# nixie_ctrl_board.net
KiCad netlist of a schematic drawn in EAGLE
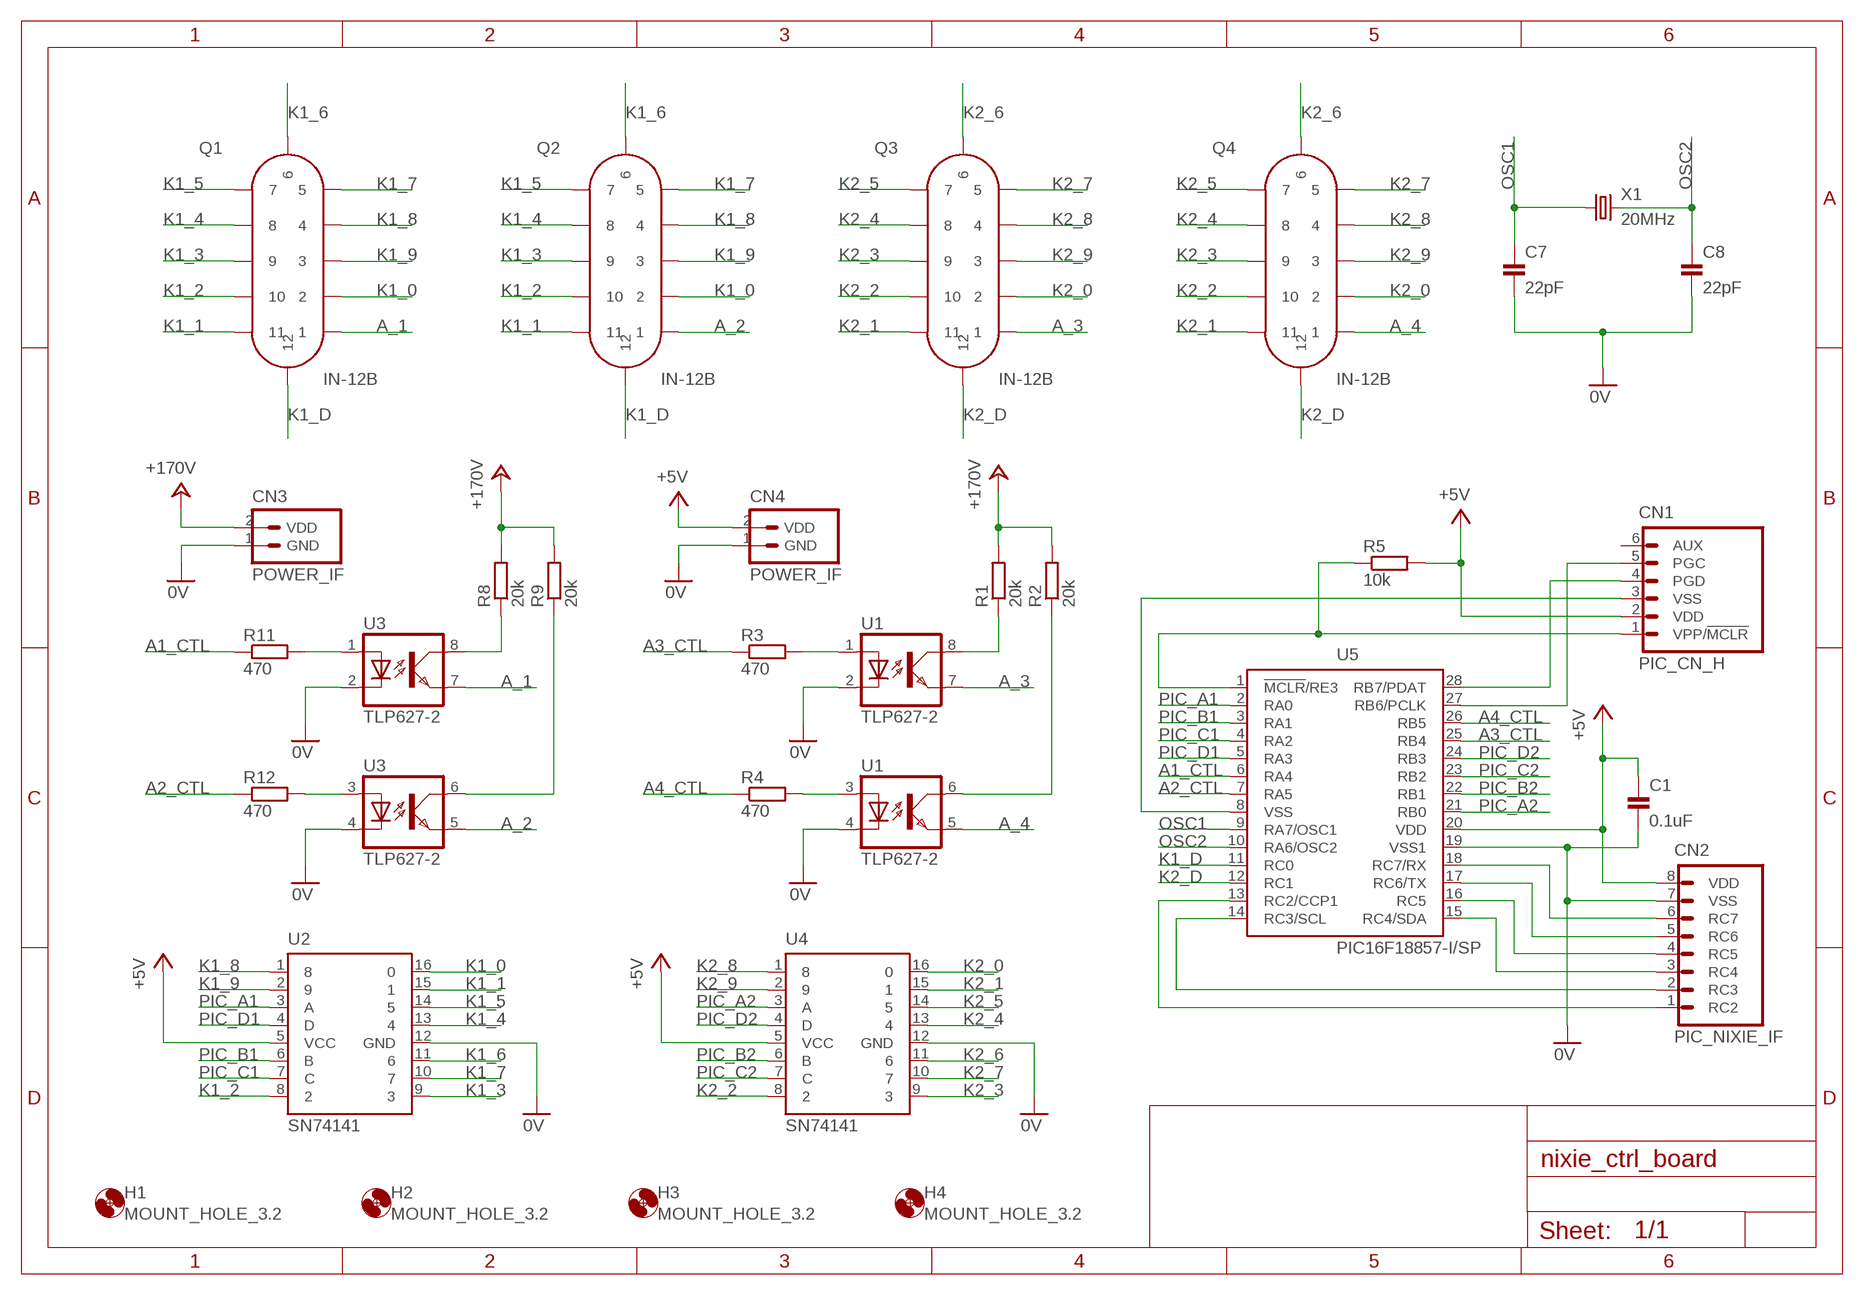
[diagram p0: schematic, sheet 1]

(export (version "E")
  (design (tool "Eeschema 10.0.6"))
  (components
    (comp (ref "C1")
      (value "0.1uF")
      (footprint "eagle-import:CAP_100MIL")
      (libsource (lib "eagle-import") (part "CAP_100MIL"))
    )
    (comp (ref "C7")
      (value "22pF")
      (footprint "eagle-import:CAP_100MIL")
      (libsource (lib "eagle-import") (part "CAP_100MIL"))
    )
    (comp (ref "C8")
      (value "22pF")
      (footprint "eagle-import:CAP_100MIL")
      (libsource (lib "eagle-import") (part "CAP_100MIL"))
    )
    (comp (ref "CN1")
      (value "PIC_CN_H")
      (footprint "eagle-import:HEADER_6PIN")
      (libsource (lib "eagle-import") (part "PIC_CN_H"))
    )
    (comp (ref "CN2")
      (value "PIC_NIXIE_IF")
      (footprint "eagle-import:PIC_IF_NIXIE_8PIN")
      (libsource (lib "eagle-import") (part "PIC_NIXIE_IF"))
    )
    (comp (ref "CN3")
      (value "POWER_IF")
      (footprint "eagle-import:HEADER_2PIN_POWER_IF")
      (libsource (lib "eagle-import") (part "POWER_IF"))
    )
    (comp (ref "CN4")
      (value "POWER_IF")
      (footprint "eagle-import:HEADER_2PIN_POWER_IF")
      (libsource (lib "eagle-import") (part "POWER_IF"))
    )
    (comp (ref "H1")
      (value "MOUNT_HOLE_3.2")
      (footprint "eagle-import:3,2")
      (libsource (lib "eagle-import") (part "MOUNT_HOLE_3.2"))
    )
    (comp (ref "H2")
      (value "MOUNT_HOLE_3.2")
      (footprint "eagle-import:3,2")
      (libsource (lib "eagle-import") (part "MOUNT_HOLE_3.2"))
    )
    (comp (ref "H3")
      (value "MOUNT_HOLE_3.2")
      (footprint "eagle-import:3,2")
      (libsource (lib "eagle-import") (part "MOUNT_HOLE_3.2"))
    )
    (comp (ref "H4")
      (value "MOUNT_HOLE_3.2")
      (footprint "eagle-import:3,2")
      (libsource (lib "eagle-import") (part "MOUNT_HOLE_3.2"))
    )
    (comp (ref "Q1")
      (value "IN-12B")
      (footprint "eagle-import:IN-12")
      (libsource (lib "eagle-import") (part "IN-12B"))
    )
    (comp (ref "Q2")
      (value "IN-12B")
      (footprint "eagle-import:IN-12")
      (libsource (lib "eagle-import") (part "IN-12B"))
    )
    (comp (ref "Q3")
      (value "IN-12B")
      (footprint "eagle-import:IN-12")
      (libsource (lib "eagle-import") (part "IN-12B"))
    )
    (comp (ref "Q4")
      (value "IN-12B")
      (footprint "eagle-import:IN-12")
      (libsource (lib "eagle-import") (part "IN-12B"))
    )
    (comp (ref "R1")
      (value "20k")
      (footprint "eagle-import:RESISTOR_0207_300MIL")
      (libsource (lib "eagle-import") (part "RESISTOR_300MIL"))
    )
    (comp (ref "R2")
      (value "20k")
      (footprint "eagle-import:RESISTOR_0207_300MIL")
      (libsource (lib "eagle-import") (part "RESISTOR_300MIL"))
    )
    (comp (ref "R3")
      (value "470")
      (footprint "eagle-import:RESISTOR_0204_200MIL")
      (libsource (lib "eagle-import") (part "RESISTOR_200MIL"))
    )
    (comp (ref "R4")
      (value "470")
      (footprint "eagle-import:RESISTOR_0204_200MIL")
      (libsource (lib "eagle-import") (part "RESISTOR_200MIL"))
    )
    (comp (ref "R5")
      (value "10k")
      (footprint "eagle-import:RESISTOR_0204_200MIL")
      (libsource (lib "eagle-import") (part "RESISTOR_200MIL"))
    )
    (comp (ref "R8")
      (value "20k")
      (footprint "eagle-import:RESISTOR_0207_300MIL")
      (libsource (lib "eagle-import") (part "RESISTOR_300MIL"))
    )
    (comp (ref "R9")
      (value "20k")
      (footprint "eagle-import:RESISTOR_0207_300MIL")
      (libsource (lib "eagle-import") (part "RESISTOR_300MIL"))
    )
    (comp (ref "R11")
      (value "470")
      (footprint "eagle-import:RESISTOR_0204_200MIL")
      (libsource (lib "eagle-import") (part "RESISTOR_200MIL"))
    )
    (comp (ref "R12")
      (value "470")
      (footprint "eagle-import:RESISTOR_0204_200MIL")
      (libsource (lib "eagle-import") (part "RESISTOR_200MIL"))
    )
    (comp (ref "U1")
      (value "TLP627-2")
      (footprint "eagle-import:DIL08")
      (libsource (lib "eagle-import") (part "TLP627-2"))
    )
    (comp (ref "U2")
      (value "SN74141")
      (footprint "eagle-import:DIL16")
      (libsource (lib "eagle-import") (part "SN74141"))
    )
    (comp (ref "U3")
      (value "TLP627-2")
      (footprint "eagle-import:DIL08")
      (libsource (lib "eagle-import") (part "TLP627-2"))
    )
    (comp (ref "U4")
      (value "SN74141")
      (footprint "eagle-import:DIL16")
      (libsource (lib "eagle-import") (part "SN74141"))
    )
    (comp (ref "U5")
      (value "PIC16F18857-I/SP")
      (footprint "eagle-import:DIL28-3")
      (libsource (lib "eagle-import") (part "PIC16F18857-I/SP"))
    )
    (comp (ref "X1")
      (value "20MHz")
      (footprint "eagle-import:HC-49_S")
      (libsource (lib "eagle-import") (part "HUSG-20.000-20"))
    )
  )
  (nets
    (net (code "1") (name "+5V") (class "Default")
      (node (ref "C1") (pin "1") (pinfunction "1_1") (pintype "passive"))
      (node (ref "CN1") (pin "2") (pinfunction "VDD_2") (pintype "passive"))
      (node (ref "CN2") (pin "8") (pinfunction "VDD_8") (pintype "passive"))
      (node (ref "CN4") (pin "2") (pinfunction "VDD_2") (pintype "passive"))
      (node (ref "R5") (pin "2") (pinfunction "2_2") (pintype "passive"))
      (node (ref "U2") (pin "5") (pinfunction "VCC_5") (pintype "passive"))
      (node (ref "U4") (pin "5") (pinfunction "VCC_5") (pintype "passive"))
      (node (ref "U5") (pin "20") (pinfunction "VDD_20") (pintype "passive"))
    )
    (net (code "2") (name "+170V") (class "Default")
      (node (ref "CN3") (pin "2") (pinfunction "VDD_2") (pintype "passive"))
      (node (ref "R1") (pin "2") (pinfunction "2_2") (pintype "passive"))
      (node (ref "R2") (pin "2") (pinfunction "2_2") (pintype "passive"))
      (node (ref "R8") (pin "2") (pinfunction "2_2") (pintype "passive"))
      (node (ref "R9") (pin "2") (pinfunction "2_2") (pintype "passive"))
    )
    (net (code "3") (name "/A1_CTL") (class "Default")
      (node (ref "R11") (pin "1") (pinfunction "1_1") (pintype "passive"))
      (node (ref "U5") (pin "6") (pinfunction "RA4_6") (pintype "bidirectional"))
    )
    (net (code "4") (name "/A2_CTL") (class "Default")
      (node (ref "R12") (pin "1") (pinfunction "1_1") (pintype "passive"))
      (node (ref "U5") (pin "7") (pinfunction "RA5_7") (pintype "bidirectional"))
    )
    (net (code "5") (name "/A3_CTL") (class "Default")
      (node (ref "R3") (pin "1") (pinfunction "1_1") (pintype "passive"))
      (node (ref "U5") (pin "25") (pinfunction "RB4_25") (pintype "bidirectional"))
    )
    (net (code "6") (name "/A4_CTL") (class "Default")
      (node (ref "R4") (pin "1") (pinfunction "1_1") (pintype "passive"))
      (node (ref "U5") (pin "26") (pinfunction "RB5_26") (pintype "bidirectional"))
    )
    (net (code "7") (name "/A_1") (class "Default")
      (node (ref "Q1") (pin "1") (pinfunction "1_1") (pintype "passive"))
      (node (ref "U3") (pin "7") (pinfunction "EMIT_7") (pintype "passive"))
    )
    (net (code "8") (name "/A_2") (class "Default")
      (node (ref "Q2") (pin "1") (pinfunction "1_1") (pintype "passive"))
      (node (ref "U3") (pin "5") (pinfunction "EMIT_5") (pintype "passive"))
    )
    (net (code "9") (name "/A_3") (class "Default")
      (node (ref "Q3") (pin "1") (pinfunction "1_1") (pintype "passive"))
      (node (ref "U1") (pin "7") (pinfunction "EMIT_7") (pintype "passive"))
    )
    (net (code "10") (name "/A_4") (class "Default")
      (node (ref "Q4") (pin "1") (pinfunction "1_1") (pintype "passive"))
      (node (ref "U1") (pin "5") (pinfunction "EMIT_5") (pintype "passive"))
    )
    (net (code "11") (name "/K1_0") (class "Default")
      (node (ref "Q1") (pin "2") (pinfunction "2_2") (pintype "passive"))
      (node (ref "Q2") (pin "2") (pinfunction "2_2") (pintype "passive"))
      (node (ref "U2") (pin "16") (pinfunction "0_16") (pintype "passive"))
    )
    (net (code "12") (name "/K1_1") (class "Default")
      (node (ref "Q1") (pin "11") (pinfunction "11_11") (pintype "passive"))
      (node (ref "Q2") (pin "11") (pinfunction "11_11") (pintype "passive"))
      (node (ref "U2") (pin "15") (pinfunction "1_15") (pintype "passive"))
    )
    (net (code "13") (name "/K1_2") (class "Default")
      (node (ref "Q1") (pin "10") (pinfunction "10_10") (pintype "passive"))
      (node (ref "Q2") (pin "10") (pinfunction "10_10") (pintype "passive"))
      (node (ref "U2") (pin "8") (pinfunction "2_8") (pintype "passive"))
    )
    (net (code "14") (name "/K1_3") (class "Default")
      (node (ref "Q1") (pin "9") (pinfunction "9_9") (pintype "passive"))
      (node (ref "Q2") (pin "9") (pinfunction "9_9") (pintype "passive"))
      (node (ref "U2") (pin "9") (pinfunction "3_9") (pintype "passive"))
    )
    (net (code "15") (name "/K1_4") (class "Default")
      (node (ref "Q1") (pin "8") (pinfunction "8_8") (pintype "passive"))
      (node (ref "Q2") (pin "8") (pinfunction "8_8") (pintype "passive"))
      (node (ref "U2") (pin "13") (pinfunction "4_13") (pintype "passive"))
    )
    (net (code "16") (name "/K1_5") (class "Default")
      (node (ref "Q1") (pin "7") (pinfunction "7_7") (pintype "passive"))
      (node (ref "Q2") (pin "7") (pinfunction "7_7") (pintype "passive"))
      (node (ref "U2") (pin "14") (pinfunction "5_14") (pintype "passive"))
    )
    (net (code "17") (name "/K1_6") (class "Default")
      (node (ref "Q1") (pin "6") (pinfunction "6_6") (pintype "passive"))
      (node (ref "Q2") (pin "6") (pinfunction "6_6") (pintype "passive"))
      (node (ref "U2") (pin "11") (pinfunction "6_11") (pintype "passive"))
    )
    (net (code "18") (name "/K1_7") (class "Default")
      (node (ref "Q1") (pin "5") (pinfunction "5_5") (pintype "passive"))
      (node (ref "Q2") (pin "5") (pinfunction "5_5") (pintype "passive"))
      (node (ref "U2") (pin "10") (pinfunction "7_10") (pintype "passive"))
    )
    (net (code "19") (name "/K1_8") (class "Default")
      (node (ref "Q1") (pin "4") (pinfunction "4_4") (pintype "passive"))
      (node (ref "Q2") (pin "4") (pinfunction "4_4") (pintype "passive"))
      (node (ref "U2") (pin "1") (pinfunction "8_1") (pintype "passive"))
    )
    (net (code "20") (name "/K1_9") (class "Default")
      (node (ref "Q1") (pin "3") (pinfunction "3_3") (pintype "passive"))
      (node (ref "Q2") (pin "3") (pinfunction "3_3") (pintype "passive"))
      (node (ref "U2") (pin "2") (pinfunction "9_2") (pintype "passive"))
    )
    (net (code "21") (name "/K1_D") (class "Default")
      (node (ref "Q1") (pin "12") (pinfunction "12_12") (pintype "passive"))
      (node (ref "Q2") (pin "12") (pinfunction "12_12") (pintype "passive"))
      (node (ref "U5") (pin "11") (pinfunction "RC0_11") (pintype "bidirectional"))
    )
    (net (code "22") (name "/K2_0") (class "Default")
      (node (ref "Q3") (pin "2") (pinfunction "2_2") (pintype "passive"))
      (node (ref "Q4") (pin "2") (pinfunction "2_2") (pintype "passive"))
      (node (ref "U4") (pin "16") (pinfunction "0_16") (pintype "passive"))
    )
    (net (code "23") (name "/K2_1") (class "Default")
      (node (ref "Q3") (pin "11") (pinfunction "11_11") (pintype "passive"))
      (node (ref "Q4") (pin "11") (pinfunction "11_11") (pintype "passive"))
      (node (ref "U4") (pin "15") (pinfunction "1_15") (pintype "passive"))
    )
    (net (code "24") (name "/K2_2") (class "Default")
      (node (ref "Q3") (pin "10") (pinfunction "10_10") (pintype "passive"))
      (node (ref "Q4") (pin "10") (pinfunction "10_10") (pintype "passive"))
      (node (ref "U4") (pin "8") (pinfunction "2_8") (pintype "passive"))
    )
    (net (code "25") (name "/K2_3") (class "Default")
      (node (ref "Q3") (pin "9") (pinfunction "9_9") (pintype "passive"))
      (node (ref "Q4") (pin "9") (pinfunction "9_9") (pintype "passive"))
      (node (ref "U4") (pin "9") (pinfunction "3_9") (pintype "passive"))
    )
    (net (code "26") (name "/K2_4") (class "Default")
      (node (ref "Q3") (pin "8") (pinfunction "8_8") (pintype "passive"))
      (node (ref "Q4") (pin "8") (pinfunction "8_8") (pintype "passive"))
      (node (ref "U4") (pin "13") (pinfunction "4_13") (pintype "passive"))
    )
    (net (code "27") (name "/K2_5") (class "Default")
      (node (ref "Q3") (pin "7") (pinfunction "7_7") (pintype "passive"))
      (node (ref "Q4") (pin "7") (pinfunction "7_7") (pintype "passive"))
      (node (ref "U4") (pin "14") (pinfunction "5_14") (pintype "passive"))
    )
    (net (code "28") (name "/K2_6") (class "Default")
      (node (ref "Q3") (pin "6") (pinfunction "6_6") (pintype "passive"))
      (node (ref "Q4") (pin "6") (pinfunction "6_6") (pintype "passive"))
      (node (ref "U4") (pin "11") (pinfunction "6_11") (pintype "passive"))
    )
    (net (code "29") (name "/K2_7") (class "Default")
      (node (ref "Q3") (pin "5") (pinfunction "5_5") (pintype "passive"))
      (node (ref "Q4") (pin "5") (pinfunction "5_5") (pintype "passive"))
      (node (ref "U4") (pin "10") (pinfunction "7_10") (pintype "passive"))
    )
    (net (code "30") (name "/K2_8") (class "Default")
      (node (ref "Q3") (pin "4") (pinfunction "4_4") (pintype "passive"))
      (node (ref "Q4") (pin "4") (pinfunction "4_4") (pintype "passive"))
      (node (ref "U4") (pin "1") (pinfunction "8_1") (pintype "passive"))
    )
    (net (code "31") (name "/K2_9") (class "Default")
      (node (ref "Q3") (pin "3") (pinfunction "3_3") (pintype "passive"))
      (node (ref "Q4") (pin "3") (pinfunction "3_3") (pintype "passive"))
      (node (ref "U4") (pin "2") (pinfunction "9_2") (pintype "passive"))
    )
    (net (code "32") (name "/K2_D") (class "Default")
      (node (ref "Q3") (pin "12") (pinfunction "12_12") (pintype "passive"))
      (node (ref "Q4") (pin "12") (pinfunction "12_12") (pintype "passive"))
      (node (ref "U5") (pin "12") (pinfunction "RC1_12") (pintype "bidirectional"))
    )
    (net (code "33") (name "/OSC1") (class "Default")
      (node (ref "C7") (pin "1") (pinfunction "1_1") (pintype "passive"))
      (node (ref "U5") (pin "9") (pinfunction "RA7/OSC1_9") (pintype "bidirectional"))
      (node (ref "X1") (pin "1") (pinfunction "1_1") (pintype "passive"))
    )
    (net (code "34") (name "/OSC2") (class "Default")
      (node (ref "C8") (pin "1") (pinfunction "1_1") (pintype "passive"))
      (node (ref "U5") (pin "10") (pinfunction "RA6/OSC2_10") (pintype "bidirectional"))
      (node (ref "X1") (pin "2") (pinfunction "2_2") (pintype "passive"))
    )
    (net (code "35") (name "/PIC_A1") (class "Default")
      (node (ref "U2") (pin "3") (pinfunction "A_3") (pintype "input"))
      (node (ref "U5") (pin "2") (pinfunction "RA0_2") (pintype "bidirectional"))
    )
    (net (code "36") (name "/PIC_A2") (class "Default")
      (node (ref "U4") (pin "3") (pinfunction "A_3") (pintype "input"))
      (node (ref "U5") (pin "21") (pinfunction "RB0_21") (pintype "bidirectional"))
    )
    (net (code "37") (name "/PIC_B1") (class "Default")
      (node (ref "U2") (pin "6") (pinfunction "B_6") (pintype "input"))
      (node (ref "U5") (pin "3") (pinfunction "RA1_3") (pintype "bidirectional"))
    )
    (net (code "38") (name "/PIC_B2") (class "Default")
      (node (ref "U4") (pin "6") (pinfunction "B_6") (pintype "input"))
      (node (ref "U5") (pin "22") (pinfunction "RB1_22") (pintype "bidirectional"))
    )
    (net (code "39") (name "/PIC_C1") (class "Default")
      (node (ref "U2") (pin "7") (pinfunction "C_7") (pintype "input"))
      (node (ref "U5") (pin "4") (pinfunction "RA2_4") (pintype "bidirectional"))
    )
    (net (code "40") (name "/PIC_C2") (class "Default")
      (node (ref "U4") (pin "7") (pinfunction "C_7") (pintype "input"))
      (node (ref "U5") (pin "23") (pinfunction "RB2_23") (pintype "bidirectional"))
    )
    (net (code "41") (name "/PIC_D1") (class "Default")
      (node (ref "U2") (pin "4") (pinfunction "D_4") (pintype "input"))
      (node (ref "U5") (pin "5") (pinfunction "RA3_5") (pintype "bidirectional"))
    )
    (net (code "42") (name "/PIC_D2") (class "Default")
      (node (ref "U4") (pin "4") (pinfunction "D_4") (pintype "input"))
      (node (ref "U5") (pin "24") (pinfunction "RB3_24") (pintype "bidirectional"))
    )
    (net (code "43") (name "0V") (class "Default")
      (node (ref "C1") (pin "2") (pinfunction "2_2") (pintype "passive"))
      (node (ref "C7") (pin "2") (pinfunction "2_2") (pintype "passive"))
      (node (ref "C8") (pin "2") (pinfunction "2_2") (pintype "passive"))
      (node (ref "CN2") (pin "7") (pinfunction "VSS_7") (pintype "passive"))
      (node (ref "CN3") (pin "1") (pinfunction "GND_1") (pintype "passive"))
      (node (ref "CN4") (pin "1") (pinfunction "GND_1") (pintype "passive"))
      (node (ref "U1") (pin "2") (pinfunction "C_2") (pintype "passive"))
      (node (ref "U1") (pin "4") (pinfunction "C_4") (pintype "passive"))
      (node (ref "U2") (pin "12") (pinfunction "GND_12") (pintype "passive"))
      (node (ref "U3") (pin "2") (pinfunction "C_2") (pintype "passive"))
      (node (ref "U3") (pin "4") (pinfunction "C_4") (pintype "passive"))
      (node (ref "U4") (pin "12") (pinfunction "GND_12") (pintype "passive"))
      (node (ref "U5") (pin "19") (pinfunction "VSS1_19") (pintype "passive"))
    )
    (net (code "44") (name "Net-(CN1-PGC)") (class "Default")
      (node (ref "CN1") (pin "5") (pinfunction "PGC_5") (pintype "input"))
      (node (ref "U5") (pin "27") (pinfunction "RB6/PCLK_27") (pintype "bidirectional"))
    )
    (net (code "45") (name "Net-(CN1-PGD)") (class "Default")
      (node (ref "CN1") (pin "4") (pinfunction "PGD_4") (pintype "bidirectional"))
      (node (ref "U5") (pin "28") (pinfunction "RB7/PDAT_28") (pintype "bidirectional"))
    )
    (net (code "46") (name "Net-(CN1-VPP{slash}~{MCLR})") (class "Default")
      (node (ref "CN1") (pin "1") (pinfunction "VPP/~{MCLR}_1") (pintype "input"))
      (node (ref "R5") (pin "1") (pinfunction "1_1") (pintype "passive"))
      (node (ref "U5") (pin "1") (pinfunction "~{MCLR}/RE3_1") (pintype "bidirectional"))
    )
    (net (code "47") (name "Net-(CN1-VSS)") (class "Default")
      (node (ref "CN1") (pin "3") (pinfunction "VSS_3") (pintype "passive"))
      (node (ref "U5") (pin "8") (pinfunction "VSS_8") (pintype "passive"))
    )
    (net (code "48") (name "Net-(CN2-RC2)") (class "Default")
      (node (ref "CN2") (pin "1") (pinfunction "RC2_1") (pintype "bidirectional"))
      (node (ref "U5") (pin "13") (pinfunction "RC2/CCP1_13") (pintype "bidirectional"))
    )
    (net (code "49") (name "Net-(CN2-RC3)") (class "Default")
      (node (ref "CN2") (pin "2") (pinfunction "RC3_2") (pintype "bidirectional"))
      (node (ref "U5") (pin "14") (pinfunction "RC3/SCL_14") (pintype "bidirectional"))
    )
    (net (code "50") (name "Net-(CN2-RC4)") (class "Default")
      (node (ref "CN2") (pin "3") (pinfunction "RC4_3") (pintype "bidirectional"))
      (node (ref "U5") (pin "15") (pinfunction "RC4/SDA_15") (pintype "bidirectional"))
    )
    (net (code "51") (name "Net-(CN2-RC5)") (class "Default")
      (node (ref "CN2") (pin "4") (pinfunction "RC5_4") (pintype "bidirectional"))
      (node (ref "U5") (pin "16") (pinfunction "RC5_16") (pintype "bidirectional"))
    )
    (net (code "52") (name "Net-(CN2-RC6)") (class "Default")
      (node (ref "CN2") (pin "5") (pinfunction "RC6_5") (pintype "bidirectional"))
      (node (ref "U5") (pin "17") (pinfunction "RC6/TX_17") (pintype "bidirectional"))
    )
    (net (code "53") (name "Net-(CN2-RC7)") (class "Default")
      (node (ref "CN2") (pin "6") (pinfunction "RC7_6") (pintype "bidirectional"))
      (node (ref "U5") (pin "18") (pinfunction "RC7/RX_18") (pintype "bidirectional"))
    )
    (net (code "54") (name "Net-(U1A-A)") (class "Default")
      (node (ref "R3") (pin "2") (pinfunction "2_2") (pintype "passive"))
      (node (ref "U1") (pin "1") (pinfunction "A_1") (pintype "passive"))
    )
    (net (code "55") (name "Net-(U1A-COL)") (class "Default")
      (node (ref "R1") (pin "1") (pinfunction "1_1") (pintype "passive"))
      (node (ref "U1") (pin "8") (pinfunction "COL_8") (pintype "passive"))
    )
    (net (code "56") (name "Net-(U1B-A)") (class "Default")
      (node (ref "R4") (pin "2") (pinfunction "2_2") (pintype "passive"))
      (node (ref "U1") (pin "3") (pinfunction "A_3") (pintype "passive"))
    )
    (net (code "57") (name "Net-(U1B-COL)") (class "Default")
      (node (ref "R2") (pin "1") (pinfunction "1_1") (pintype "passive"))
      (node (ref "U1") (pin "6") (pinfunction "COL_6") (pintype "passive"))
    )
    (net (code "58") (name "Net-(U3A-A)") (class "Default")
      (node (ref "R11") (pin "2") (pinfunction "2_2") (pintype "passive"))
      (node (ref "U3") (pin "1") (pinfunction "A_1") (pintype "passive"))
    )
    (net (code "59") (name "Net-(U3A-COL)") (class "Default")
      (node (ref "R8") (pin "1") (pinfunction "1_1") (pintype "passive"))
      (node (ref "U3") (pin "8") (pinfunction "COL_8") (pintype "passive"))
    )
    (net (code "60") (name "Net-(U3B-A)") (class "Default")
      (node (ref "R12") (pin "2") (pinfunction "2_2") (pintype "passive"))
      (node (ref "U3") (pin "3") (pinfunction "A_3") (pintype "passive"))
    )
    (net (code "61") (name "Net-(U3B-COL)") (class "Default")
      (node (ref "R9") (pin "1") (pinfunction "1_1") (pintype "passive"))
      (node (ref "U3") (pin "6") (pinfunction "COL_6") (pintype "passive"))
    )
    (net (code "62") (name "unconnected-(CN1-AUX-Pad6)") (class "Default")
      (node (ref "CN1") (pin "6") (pinfunction "AUX_6") (pintype "bidirectional"))
    )
  )
)
